# basic_duino.net
KiCad netlist of a schematic drawn in EAGLE
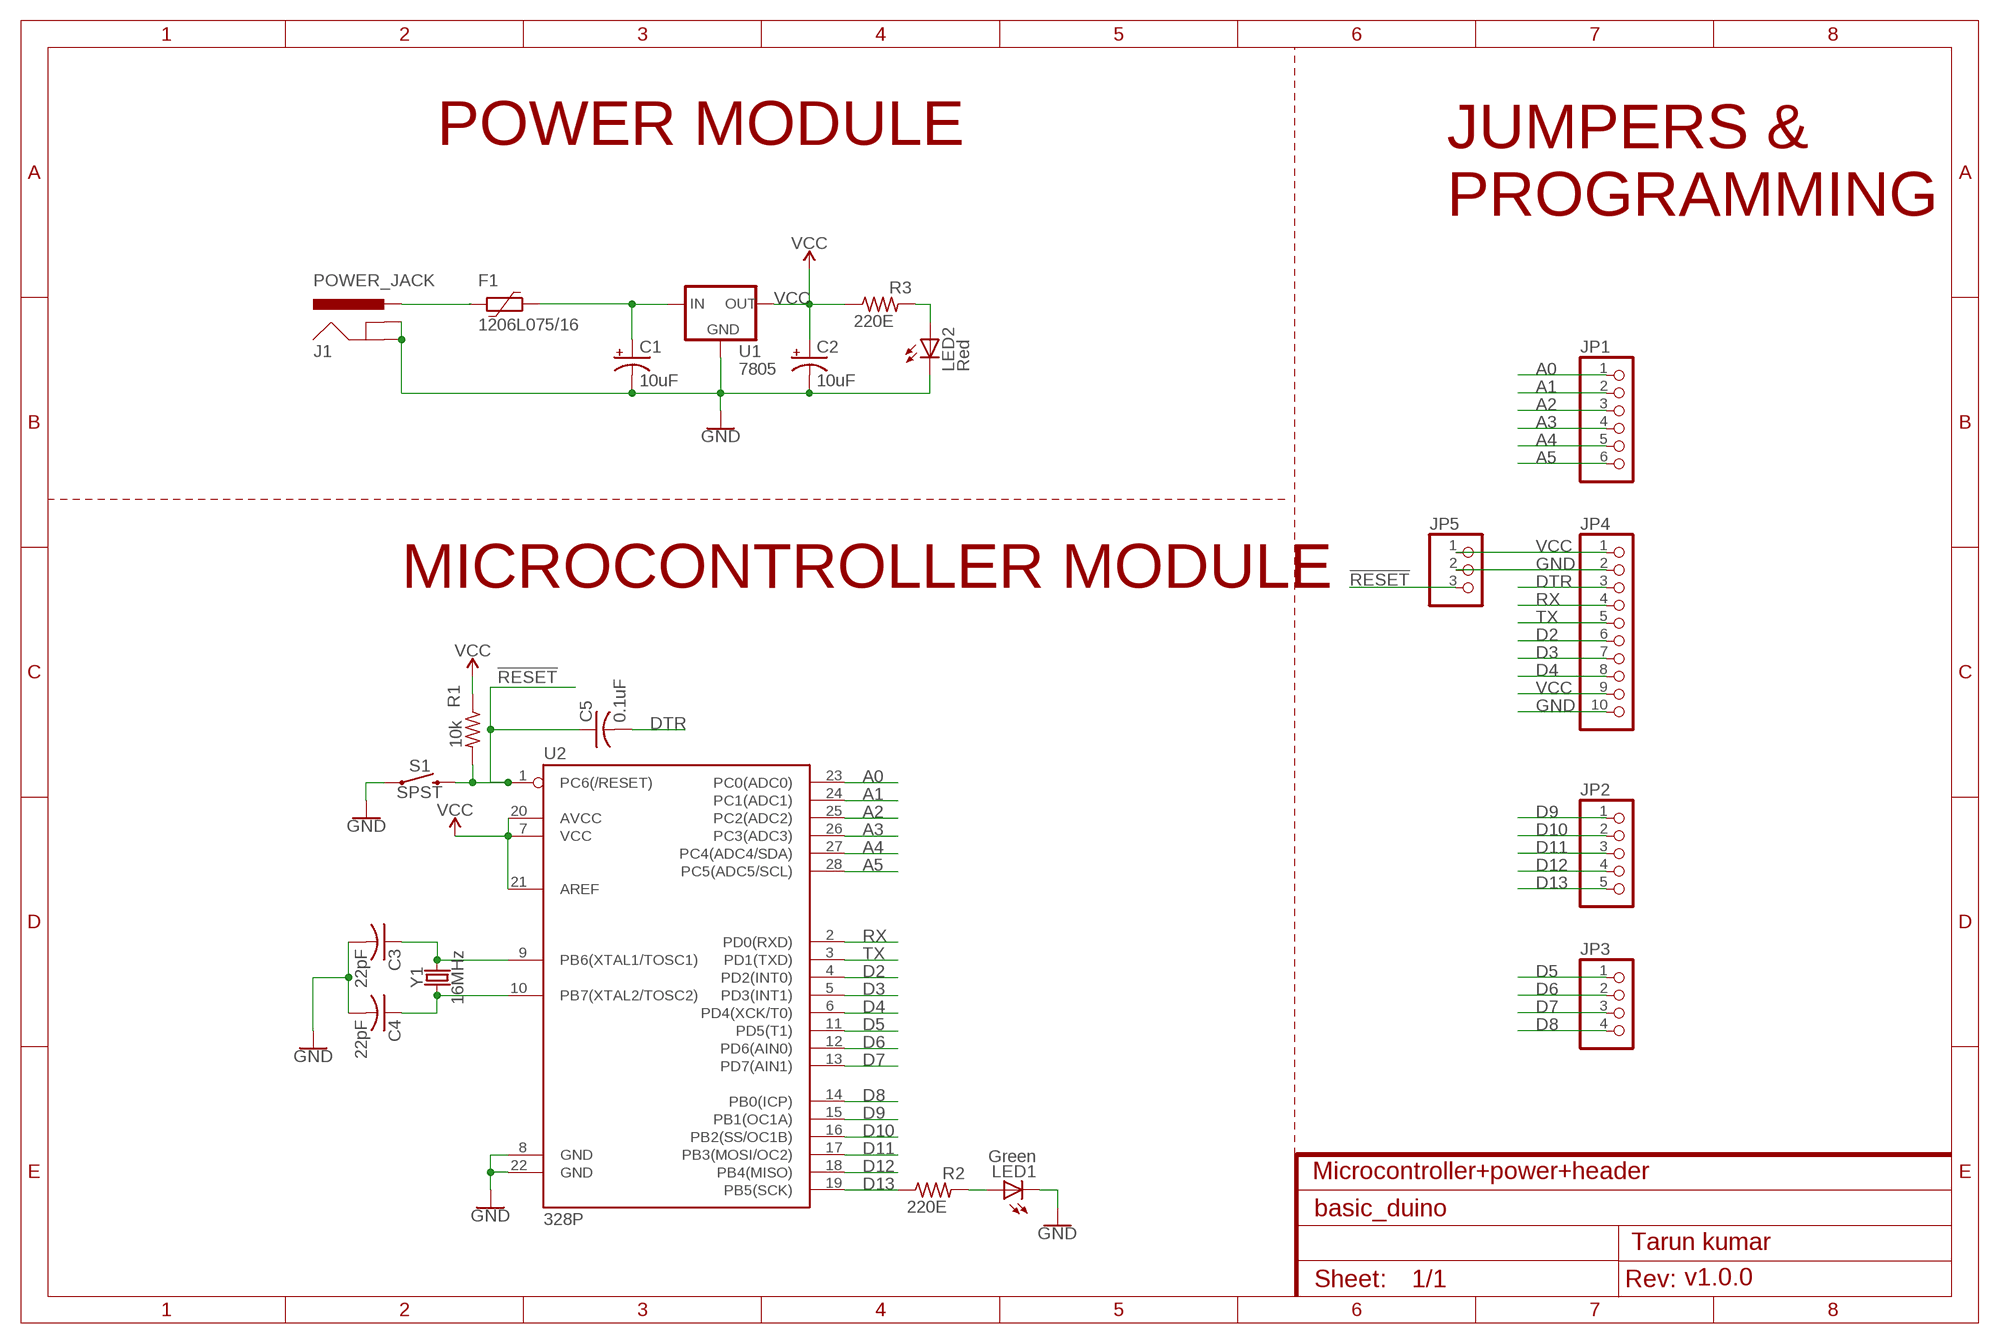
[diagram p0: schematic, sheet 1]

(export (version "E")
  (design (tool "Eeschema 10.0.6"))
  (components
    (comp (ref "C1")
      (value "10uF")
      (footprint "eagle-import:E2,5-6")
      (libsource (lib "eagle-import") (part "CPOL-USE2.5-6"))
    )
    (comp (ref "C2")
      (value "10uF")
      (footprint "eagle-import:E2,5-6")
      (libsource (lib "eagle-import") (part "CPOL-USE2.5-6"))
    )
    (comp (ref "C3")
      (value "22pF")
      (footprint "eagle-import:C025-025X050")
      (libsource (lib "eagle-import") (part "C-US025-025X050"))
    )
    (comp (ref "C4")
      (value "22pF")
      (footprint "eagle-import:C025-025X050")
      (libsource (lib "eagle-import") (part "C-US025-025X050"))
    )
    (comp (ref "C5")
      (value "0.1uF")
      (footprint "eagle-import:C025-025X050")
      (libsource (lib "eagle-import") (part "C-US025-025X050"))
    )
    (comp (ref "F1")
      (value "1206L075/16")
      (footprint "eagle-import:1206L")
      (fields (field (name "MF") "Littelfuse"))
      (libsource (lib "eagle-import") (part "?1206L075/16"))
    )
    (comp (ref "J1")
      (value "POWER_JACK")
      (footprint "eagle-import:POWER_JACK_PTH")
      (libsource (lib "eagle-import") (part "POWER_JACK"))
    )
    (comp (ref "JP1")
      (value "PINHD-1X6")
      (footprint "eagle-import:1X06")
      (libsource (lib "eagle-import") (part "PINHD-1X6"))
    )
    (comp (ref "JP2")
      (value "PINHD-1X5")
      (footprint "eagle-import:1X05")
      (libsource (lib "eagle-import") (part "PINHD-1X5"))
    )
    (comp (ref "JP3")
      (value "PINHD-1X4")
      (footprint "eagle-import:1X04")
      (libsource (lib "eagle-import") (part "PINHD-1X4"))
    )
    (comp (ref "JP4")
      (value "PINHD-1X10")
      (footprint "eagle-import:1X10")
      (libsource (lib "eagle-import") (part "PINHD-1X10"))
    )
    (comp (ref "JP5")
      (value "PINHD-1X3")
      (footprint "eagle-import:1X03")
      (libsource (lib "eagle-import") (part "PINHD-1X3"))
    )
    (comp (ref "LED1")
      (value "Green")
      (footprint "eagle-import:LED3MM")
      (libsource (lib "eagle-import") (part "LED3MM"))
    )
    (comp (ref "LED2")
      (value "Red")
      (footprint "eagle-import:LED3MM")
      (libsource (lib "eagle-import") (part "LED3MM"))
    )
    (comp (ref "R1")
      (value "10k")
      (footprint "eagle-import:0204_7")
      (libsource (lib "eagle-import") (part "R-US_0204/7"))
    )
    (comp (ref "R2")
      (value "220E")
      (footprint "eagle-import:0204_7")
      (libsource (lib "eagle-import") (part "R-US_0204/7"))
    )
    (comp (ref "R3")
      (value "220E")
      (footprint "eagle-import:0204_7")
      (libsource (lib "eagle-import") (part "R-US_0204/7"))
    )
    (comp (ref "S1")
      (value "SPST")
      (footprint "eagle-import:TACTILE_SWITCH_PTH_6.0MM")
      (libsource (lib "eagle-import") (part "MOMENTARY-SWITCH-SPST-PTH-6.0MM"))
    )
    (comp (ref "U1")
      (value "7805")
      (footprint "eagle-import:78XXS")
      (libsource (lib "eagle-import") (part "78XXS"))
    )
    (comp (ref "U2")
      (value "328P")
      (footprint "eagle-import:DIP28")
      (libsource (lib "eagle-import") (part "ATMEGA328P_PDIP"))
    )
    (comp (ref "Y1")
      (value "16MHz")
      (footprint "eagle-import:HC49US")
      (libsource (lib "eagle-import") (part "CRYSTAL-16MHZPTH-HC49US"))
    )
  )
  (nets
    (net (code "1") (name "/A0") (class "Default")
      (node (ref "JP1") (pin "1") (pinfunction "1_1") (pintype "passive"))
      (node (ref "U2") (pin "23") (pinfunction "PC0(ADC0)_23") (pintype "bidirectional"))
    )
    (net (code "2") (name "/A1") (class "Default")
      (node (ref "JP1") (pin "2") (pinfunction "2_2") (pintype "passive"))
      (node (ref "U2") (pin "24") (pinfunction "PC1(ADC1)_24") (pintype "bidirectional"))
    )
    (net (code "3") (name "/A2") (class "Default")
      (node (ref "JP1") (pin "3") (pinfunction "3_3") (pintype "passive"))
      (node (ref "U2") (pin "25") (pinfunction "PC2(ADC2)_25") (pintype "bidirectional"))
    )
    (net (code "4") (name "/A3") (class "Default")
      (node (ref "JP1") (pin "4") (pinfunction "4_4") (pintype "passive"))
      (node (ref "U2") (pin "26") (pinfunction "PC3(ADC3)_26") (pintype "bidirectional"))
    )
    (net (code "5") (name "/A4") (class "Default")
      (node (ref "JP1") (pin "5") (pinfunction "5_5") (pintype "passive"))
      (node (ref "U2") (pin "27") (pinfunction "PC4(ADC4/SDA)_27") (pintype "bidirectional"))
    )
    (net (code "6") (name "/A5") (class "Default")
      (node (ref "JP1") (pin "6") (pinfunction "6_6") (pintype "passive"))
      (node (ref "U2") (pin "28") (pinfunction "PC5(ADC5/SCL)_28") (pintype "bidirectional"))
    )
    (net (code "7") (name "/D2") (class "Default")
      (node (ref "JP4") (pin "6") (pinfunction "6_6") (pintype "passive"))
      (node (ref "U2") (pin "4") (pinfunction "PD2(INT0)_4") (pintype "bidirectional"))
    )
    (net (code "8") (name "/D3") (class "Default")
      (node (ref "JP4") (pin "7") (pinfunction "7_7") (pintype "passive"))
      (node (ref "U2") (pin "5") (pinfunction "PD3(INT1)_5") (pintype "bidirectional"))
    )
    (net (code "9") (name "/D4") (class "Default")
      (node (ref "JP4") (pin "8") (pinfunction "8_8") (pintype "passive"))
      (node (ref "U2") (pin "6") (pinfunction "PD4(XCK/T0)_6") (pintype "bidirectional"))
    )
    (net (code "10") (name "/D5") (class "Default")
      (node (ref "JP3") (pin "1") (pinfunction "1_1") (pintype "passive"))
      (node (ref "U2") (pin "11") (pinfunction "PD5(T1)_11") (pintype "bidirectional"))
    )
    (net (code "11") (name "/D6") (class "Default")
      (node (ref "JP3") (pin "2") (pinfunction "2_2") (pintype "passive"))
      (node (ref "U2") (pin "12") (pinfunction "PD6(AIN0)_12") (pintype "bidirectional"))
    )
    (net (code "12") (name "/D7") (class "Default")
      (node (ref "JP3") (pin "3") (pinfunction "3_3") (pintype "passive"))
      (node (ref "U2") (pin "13") (pinfunction "PD7(AIN1)_13") (pintype "bidirectional"))
    )
    (net (code "13") (name "/D8") (class "Default")
      (node (ref "JP3") (pin "4") (pinfunction "4_4") (pintype "passive"))
      (node (ref "U2") (pin "14") (pinfunction "PB0(ICP)_14") (pintype "bidirectional"))
    )
    (net (code "14") (name "/D9") (class "Default")
      (node (ref "JP2") (pin "1") (pinfunction "1_1") (pintype "passive"))
      (node (ref "U2") (pin "15") (pinfunction "PB1(OC1A)_15") (pintype "bidirectional"))
    )
    (net (code "15") (name "/D10") (class "Default")
      (node (ref "JP2") (pin "2") (pinfunction "2_2") (pintype "passive"))
      (node (ref "U2") (pin "16") (pinfunction "PB2(SS/OC1B)_16") (pintype "bidirectional"))
    )
    (net (code "16") (name "/D11") (class "Default")
      (node (ref "JP2") (pin "3") (pinfunction "3_3") (pintype "passive"))
      (node (ref "U2") (pin "17") (pinfunction "PB3(MOSI/OC2)_17") (pintype "bidirectional"))
    )
    (net (code "17") (name "/D12") (class "Default")
      (node (ref "JP2") (pin "4") (pinfunction "4_4") (pintype "passive"))
      (node (ref "U2") (pin "18") (pinfunction "PB4(MISO)_18") (pintype "bidirectional"))
    )
    (net (code "18") (name "/D13") (class "Default")
      (node (ref "JP2") (pin "5") (pinfunction "5_5") (pintype "passive"))
      (node (ref "R2") (pin "1") (pinfunction "1_1") (pintype "passive"))
      (node (ref "U2") (pin "19") (pinfunction "PB5(SCK)_19") (pintype "bidirectional"))
    )
    (net (code "19") (name "/DTR") (class "Default")
      (node (ref "C5") (pin "2") (pinfunction "2_2") (pintype "passive"))
      (node (ref "JP4") (pin "3") (pinfunction "3_3") (pintype "passive"))
    )
    (net (code "20") (name "/RX") (class "Default")
      (node (ref "JP4") (pin "4") (pinfunction "4_4") (pintype "passive"))
      (node (ref "U2") (pin "2") (pinfunction "PD0(RXD)_2") (pintype "bidirectional"))
    )
    (net (code "21") (name "/TX") (class "Default")
      (node (ref "JP4") (pin "5") (pinfunction "5_5") (pintype "passive"))
      (node (ref "U2") (pin "3") (pinfunction "PD1(TXD)_3") (pintype "bidirectional"))
    )
    (net (code "22") (name "/~{RESET}") (class "Default")
      (node (ref "C5") (pin "1") (pinfunction "1_1") (pintype "passive"))
      (node (ref "JP5") (pin "3") (pinfunction "3_3") (pintype "passive"))
      (node (ref "R1") (pin "2") (pinfunction "2_2") (pintype "passive"))
      (node (ref "S1") (pin "3") (pinfunction "2_3") (pintype "passive"))
      (node (ref "U2") (pin "1") (pinfunction "PC6(/RESET)_1") (pintype "bidirectional"))
    )
    (net (code "23") (name "GND") (class "Default")
      (node (ref "C1") (pin "-") (pinfunction "-_-") (pintype "passive"))
      (node (ref "C2") (pin "-") (pinfunction "-_-") (pintype "passive"))
      (node (ref "C3") (pin "2") (pinfunction "2_2") (pintype "passive"))
      (node (ref "C4") (pin "2") (pinfunction "2_2") (pintype "passive"))
      (node (ref "J1") (pin "GND") (pinfunction "GND_GND") (pintype "bidirectional"))
      (node (ref "J1") (pin "GNDBREAK") (pinfunction "GNDBREAK_GNDBREAK") (pintype "bidirectional"))
      (node (ref "JP4") (pin "10") (pinfunction "10_10") (pintype "passive"))
      (node (ref "JP4") (pin "2") (pinfunction "2_2") (pintype "passive"))
      (node (ref "JP5") (pin "2") (pinfunction "2_2") (pintype "passive"))
      (node (ref "LED1") (pin "K") (pinfunction "C_K") (pintype "passive"))
      (node (ref "LED2") (pin "K") (pinfunction "C_K") (pintype "passive"))
      (node (ref "S1") (pin "1") (pinfunction "1_1") (pintype "passive"))
      (node (ref "U1") (pin "GND") (pinfunction "GND_GND") (pintype "input"))
      (node (ref "U2") (pin "22") (pinfunction "GND_22") (pintype "bidirectional"))
      (node (ref "U2") (pin "8") (pinfunction "GND_8") (pintype "bidirectional"))
    )
    (net (code "24") (name "Net-(C1-Pad+)") (class "Default")
      (node (ref "C1") (pin "+") (pinfunction "+_+") (pintype "passive"))
      (node (ref "F1") (pin "1") (pinfunction "1_1") (pintype "passive"))
      (node (ref "U1") (pin "IN") (pinfunction "IN_IN") (pintype "input"))
    )
    (net (code "25") (name "Net-(F1-Pad2)") (class "Default")
      (node (ref "F1") (pin "2") (pinfunction "2_2") (pintype "passive"))
      (node (ref "J1") (pin "PWR") (pinfunction "PWR_PWR") (pintype "bidirectional"))
    )
    (net (code "26") (name "Net-(LED1-PadA)") (class "Default")
      (node (ref "LED1") (pin "A") (pinfunction "A_A") (pintype "passive"))
      (node (ref "R2") (pin "2") (pinfunction "2_2") (pintype "passive"))
    )
    (net (code "27") (name "Net-(LED2-PadA)") (class "Default")
      (node (ref "LED2") (pin "A") (pinfunction "A_A") (pintype "passive"))
      (node (ref "R3") (pin "2") (pinfunction "2_2") (pintype "passive"))
    )
    (net (code "28") (name "Net-(U2-PB6(XTAL1{slash}TOSC1))") (class "Default")
      (node (ref "C3") (pin "1") (pinfunction "1_1") (pintype "passive"))
      (node (ref "U2") (pin "9") (pinfunction "PB6(XTAL1/TOSC1)_9") (pintype "bidirectional"))
      (node (ref "Y1") (pin "2") (pinfunction "2_2") (pintype "passive"))
    )
    (net (code "29") (name "Net-(U2-PB7(XTAL2{slash}TOSC2))") (class "Default")
      (node (ref "C4") (pin "1") (pinfunction "1_1") (pintype "passive"))
      (node (ref "U2") (pin "10") (pinfunction "PB7(XTAL2/TOSC2)_10") (pintype "bidirectional"))
      (node (ref "Y1") (pin "1") (pinfunction "1_1") (pintype "passive"))
    )
    (net (code "30") (name "VCC") (class "Default")
      (node (ref "C2") (pin "+") (pinfunction "+_+") (pintype "passive"))
      (node (ref "JP4") (pin "1") (pinfunction "1_1") (pintype "passive"))
      (node (ref "JP4") (pin "9") (pinfunction "9_9") (pintype "passive"))
      (node (ref "JP5") (pin "1") (pinfunction "1_1") (pintype "passive"))
      (node (ref "R1") (pin "1") (pinfunction "1_1") (pintype "passive"))
      (node (ref "R3") (pin "1") (pinfunction "1_1") (pintype "passive"))
      (node (ref "U1") (pin "OUT") (pinfunction "OUT_OUT") (pintype "passive"))
      (node (ref "U2") (pin "20") (pinfunction "AVCC_20") (pintype "bidirectional"))
      (node (ref "U2") (pin "21") (pinfunction "AREF_21") (pintype "bidirectional"))
      (node (ref "U2") (pin "7") (pinfunction "VCC_7") (pintype "bidirectional"))
    )
  )
)
